# StereoHeadphoneDriver.net
KiCad netlist of a schematic drawn in Altium Designer
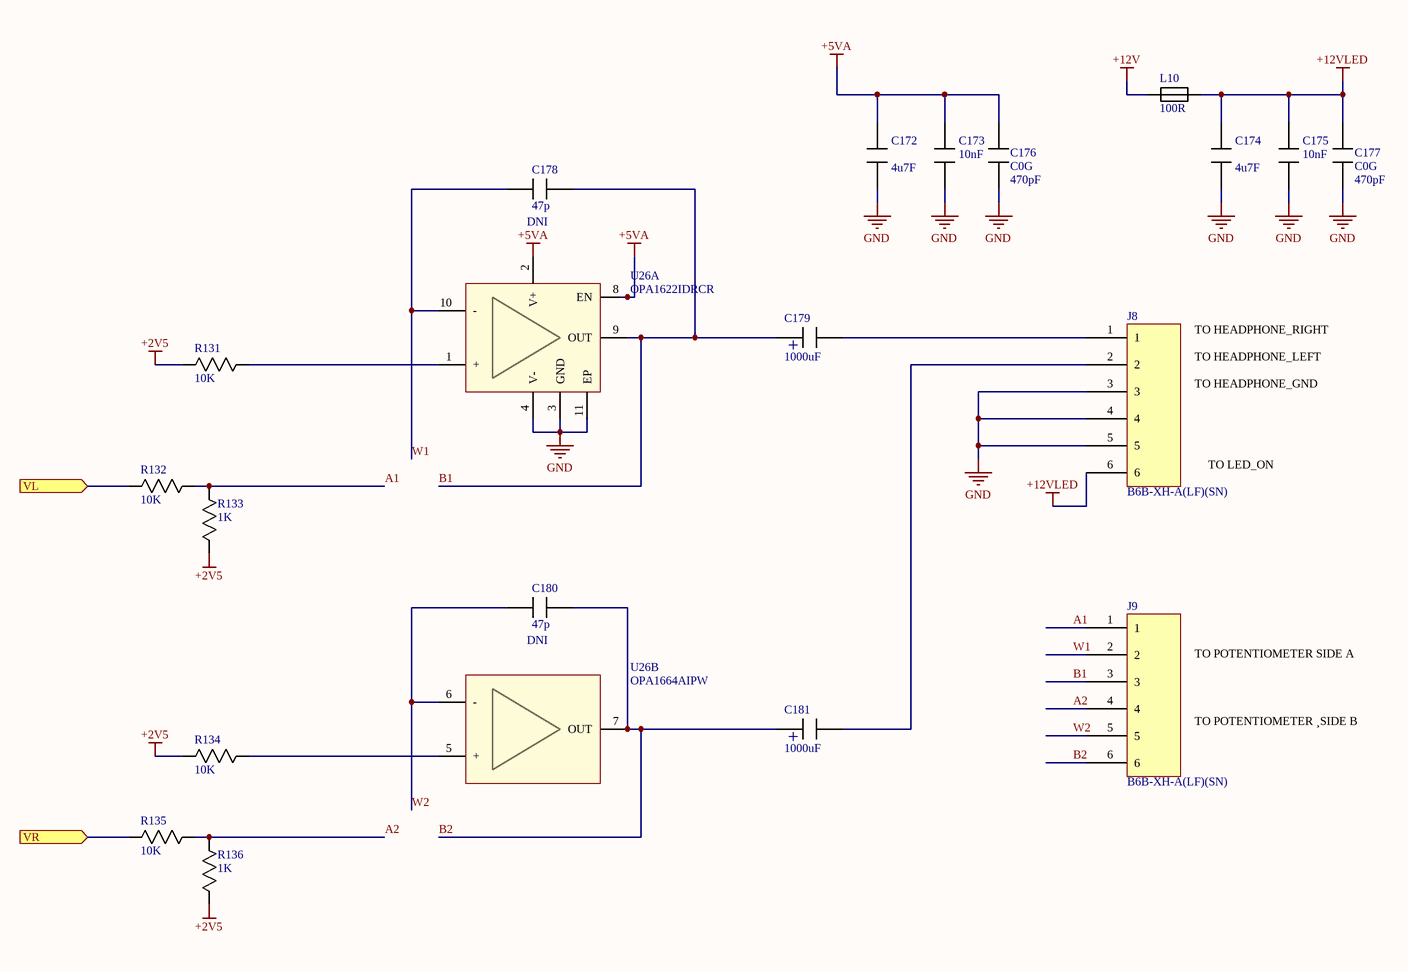
[diagram p0: StereoHeadphoneDriver.SchDoc]

(export (version "E")
  (design (tool "Eeschema 10.0.6"))
  (components
    (comp (ref "C172")
      (value "4u7F")
      (footprint "0805")
      (description "Capacitor")
      (fields (field (name "MFG") "Samsung"))
      (libsource (lib "ADAPTONE_CARTE_DE_SON") (part "Capacitor"))
    )
    (comp (ref "C173")
      (value "10nF")
      (footprint "0603")
      (description "Capacitor")
      (fields (field (name "MFG") "Murata"))
      (libsource (lib "ADAPTONE_CARTE_DE_SON") (part "Capacitor"))
    )
    (comp (ref "C174")
      (value "4u7F")
      (footprint "0805")
      (description "Capacitor")
      (fields (field (name "MFG") "Samsung"))
      (libsource (lib "ADAPTONE_CARTE_DE_SON") (part "Capacitor"))
    )
    (comp (ref "C175")
      (value "10nF")
      (footprint "0603")
      (description "Capacitor")
      (fields (field (name "MFG") "Murata"))
      (libsource (lib "ADAPTONE_CARTE_DE_SON") (part "Capacitor"))
    )
    (comp (ref "C176")
      (value "470pF")
      (footprint "0603")
      (description "Capacitor")
      (fields (field (name "MFG") "Samsung") (field (name "TYPE") "C0G"))
      (libsource (lib "ADAPTONE_CARTE_DE_SON") (part "Capacitor"))
    )
    (comp (ref "C177")
      (value "470pF")
      (footprint "0603")
      (description "Capacitor")
      (fields (field (name "MFG") "Samsung") (field (name "TYPE") "C0G"))
      (libsource (lib "ADAPTONE_CARTE_DE_SON") (part "Capacitor"))
    )
    (comp (ref "C178")
      (value "47p")
      (footprint "0402")
      (description "Capacitor")
      (fields (field (name "MFG") "Murata") (field (name "NOTE") "DNI"))
      (libsource (lib "LIB_ADAPTONE_PASCAL_LEMIEUX") (part "Capacitor"))
    )
    (comp (ref "C179")
      (value "1000uF")
      (footprint "CAP_RAD_SMD_DIA315")
      (description "Capacitor")
      (fields (field (name "MFG") "Nichicon") (field (name "Comment") "Capacitor_Polarized"))
      (libsource (lib "ADAPTONE_CARTE_DE_SON") (part "Capacitor_Polarized_1"))
    )
    (comp (ref "C180")
      (value "47p")
      (footprint "0402")
      (description "Capacitor")
      (fields (field (name "MFG") "Murata") (field (name "NOTE") "DNI"))
      (libsource (lib "LIB_ADAPTONE_PASCAL_LEMIEUX") (part "Capacitor"))
    )
    (comp (ref "C181")
      (value "1000uF")
      (footprint "CAP_RAD_SMD_DIA315")
      (description "Capacitor")
      (fields (field (name "MFG") "Nichicon") (field (name "Comment") "Capacitor_Polarized"))
      (libsource (lib "ADAPTONE_CARTE_DE_SON") (part "Capacitor_Polarized_1"))
    )
    (comp (ref "J8")
      (value "CON_XH_JST_6pins")
      (footprint "CONN_6_HEADER")
      (fields (field (name "MFG") "JST Sales America Inc.") (field (name "MFG_PN") "B6B-XH-A(LF)(SN)"))
      (libsource (lib "LIB_ADAPTONE_PASCAL_LEMIEUX") (part "CON_XH_JST_6pins"))
    )
    (comp (ref "J9")
      (value "CON_XH_JST_6pins")
      (footprint "CONN_6_HEADER")
      (fields (field (name "MFG") "JST Sales America Inc.") (field (name "MFG_PN") "B6B-XH-A(LF)(SN)"))
      (libsource (lib "LIB_ADAPTONE_PASCAL_LEMIEUX") (part "CON_XH_JST_6pins"))
    )
    (comp (ref "L10")
      (value "100R")
      (footprint "0603")
      (description "Ferrite")
      (fields (field (name "MFG") "Bourns"))
      (libsource (lib "ADAPTONE_CARTE_DE_SON") (part "Ferrite"))
    )
    (comp (ref "R131")
      (value "10K")
      (footprint "0402")
      (description "Resistor")
      (fields (field (name "MFG") "Yageo"))
      (libsource (lib "LIB_ADAPTONE_PASCAL_LEMIEUX") (part "Resistor"))
    )
    (comp (ref "R132")
      (value "10K")
      (footprint "0402")
      (description "Resistor")
      (fields (field (name "MFG") "Yageo"))
      (libsource (lib "LIB_ADAPTONE_PASCAL_LEMIEUX") (part "Resistor"))
    )
    (comp (ref "R133")
      (value "1K")
      (footprint "0402")
      (description "Resistor")
      (fields (field (name "MFG") "Yageo"))
      (libsource (lib "LIB_ADAPTONE_PASCAL_LEMIEUX") (part "Resistor"))
    )
    (comp (ref "R134")
      (value "10K")
      (footprint "0402")
      (description "Resistor")
      (fields (field (name "MFG") "Yageo"))
      (libsource (lib "LIB_ADAPTONE_PASCAL_LEMIEUX") (part "Resistor"))
    )
    (comp (ref "R135")
      (value "10K")
      (footprint "0402")
      (description "Resistor")
      (fields (field (name "MFG") "Yageo"))
      (libsource (lib "LIB_ADAPTONE_PASCAL_LEMIEUX") (part "Resistor"))
    )
    (comp (ref "R136")
      (value "1K")
      (footprint "0402")
      (description "Resistor")
      (fields (field (name "MFG") "Yageo"))
      (libsource (lib "LIB_ADAPTONE_PASCAL_LEMIEUX") (part "Resistor"))
    )
    (comp (ref "U26")
      (value "OPA1622")
      (footprint "10-VFDFN")
      (description "Dual amplifier (headphone driver)")
      (fields (field (name "MFG") "Texas Instruments") (field (name "MFG_PN") "OPA1622IDRCR"))
      (libsource (lib "LIB_ADAPTONE_PASCAL_LEMIEUX") (part "OPA1622"))
    )
  )
  (nets
    (net (code "1") (name "+2V5") (class "Default")
      (node (ref "R131") (pin "2") (pintype "passive"))
      (node (ref "R133") (pin "2") (pintype "passive"))
      (node (ref "R134") (pin "2") (pintype "passive"))
      (node (ref "R136") (pin "2") (pintype "passive"))
    )
    (net (code "2") (name "+5VA") (class "Default")
      (node (ref "C172") (pin "1") (pintype "passive"))
      (node (ref "C173") (pin "1") (pintype "passive"))
      (node (ref "C176") (pin "2") (pintype "passive"))
      (node (ref "U26") (pin "2") (pinfunction "V+_2") (pintype "passive"))
      (node (ref "U26") (pin "8") (pinfunction "EN_8") (pintype "passive"))
    )
    (net (code "3") (name "+12V") (class "Default") (node (ref "L10") (pin "1") (pintype "passive")))
    (net (code "4") (name "+12VLED") (class "Default")
      (node (ref "C174") (pin "1") (pintype "passive"))
      (node (ref "C175") (pin "1") (pintype "passive"))
      (node (ref "C177") (pin "2") (pintype "passive"))
      (node (ref "J8") (pin "6") (pinfunction "6_6") (pintype "passive"))
      (node (ref "L10") (pin "2") (pintype "passive"))
    )
    (net (code "5") (name "/A1") (class "Default")
      (node (ref "J9") (pin "1") (pinfunction "1_1") (pintype "passive"))
      (node (ref "R132") (pin "1") (pintype "passive"))
      (node (ref "R133") (pin "1") (pintype "passive"))
    )
    (net (code "6") (name "/A2") (class "Default")
      (node (ref "J9") (pin "4") (pinfunction "4_4") (pintype "passive"))
      (node (ref "R135") (pin "1") (pintype "passive"))
      (node (ref "R136") (pin "1") (pintype "passive"))
    )
    (net (code "7") (name "/B1") (class "Default")
      (node (ref "C178") (pin "2") (pintype "passive"))
      (node (ref "C179") (pin "+") (pintype "passive"))
      (node (ref "J9") (pin "3") (pinfunction "3_3") (pintype "passive"))
      (node (ref "U26") (pin "9") (pinfunction "OUT_9") (pintype "passive"))
    )
    (net (code "8") (name "/B2") (class "Default")
      (node (ref "C180") (pin "2") (pintype "passive"))
      (node (ref "C181") (pin "+") (pintype "passive"))
      (node (ref "J9") (pin "6") (pinfunction "6_6") (pintype "passive"))
      (node (ref "U26") (pin "7") (pinfunction "OUT_7") (pintype "passive"))
    )
    (net (code "9") (name "/VL") (class "Default") (node (ref "R132") (pin "2") (pintype "passive")))
    (net (code "10") (name "/VR") (class "Default") (node (ref "R135") (pin "2") (pintype "passive")))
    (net (code "11") (name "/W1") (class "Default")
      (node (ref "C178") (pin "1") (pintype "passive"))
      (node (ref "J9") (pin "2") (pinfunction "2_2") (pintype "passive"))
      (node (ref "U26") (pin "10") (pinfunction "-_10") (pintype "passive"))
    )
    (net (code "12") (name "/W2") (class "Default")
      (node (ref "C180") (pin "1") (pintype "passive"))
      (node (ref "J9") (pin "5") (pinfunction "5_5") (pintype "passive"))
      (node (ref "U26") (pin "6") (pinfunction "-_6") (pintype "passive"))
    )
    (net (code "13") (name "GND") (class "Default")
      (node (ref "C172") (pin "2") (pintype "passive"))
      (node (ref "C173") (pin "2") (pintype "passive"))
      (node (ref "C174") (pin "2") (pintype "passive"))
      (node (ref "C175") (pin "2") (pintype "passive"))
      (node (ref "C176") (pin "1") (pintype "passive"))
      (node (ref "C177") (pin "1") (pintype "passive"))
      (node (ref "J8") (pin "3") (pinfunction "3_3") (pintype "passive"))
      (node (ref "J8") (pin "4") (pinfunction "4_4") (pintype "passive"))
      (node (ref "J8") (pin "5") (pinfunction "5_5") (pintype "passive"))
      (node (ref "U26") (pin "11") (pinfunction "EP_11") (pintype "passive"))
      (node (ref "U26") (pin "3") (pinfunction "GND_3") (pintype "passive"))
      (node (ref "U26") (pin "4") (pinfunction "V-_4") (pintype "passive"))
    )
    (net (code "14") (name "Net-(C179-Pad-)") (class "Default")
      (node (ref "C179") (pin "-") (pintype "passive"))
      (node (ref "J8") (pin "1") (pinfunction "1_1") (pintype "passive"))
    )
    (net (code "15") (name "Net-(C181-Pad-)") (class "Default")
      (node (ref "C181") (pin "-") (pintype "passive"))
      (node (ref "J8") (pin "2") (pinfunction "2_2") (pintype "passive"))
    )
    (net (code "16") (name "Net-(U26A-+)") (class "Default")
      (node (ref "R131") (pin "1") (pintype "passive"))
      (node (ref "U26") (pin "1") (pinfunction "+_1") (pintype "passive"))
    )
    (net (code "17") (name "Net-(U26B-+)") (class "Default")
      (node (ref "R134") (pin "1") (pintype "passive"))
      (node (ref "U26") (pin "5") (pinfunction "+_5") (pintype "passive"))
    )
  )
)
